# schematic.net
KiCad netlist of a schematic drawn in EAGLE
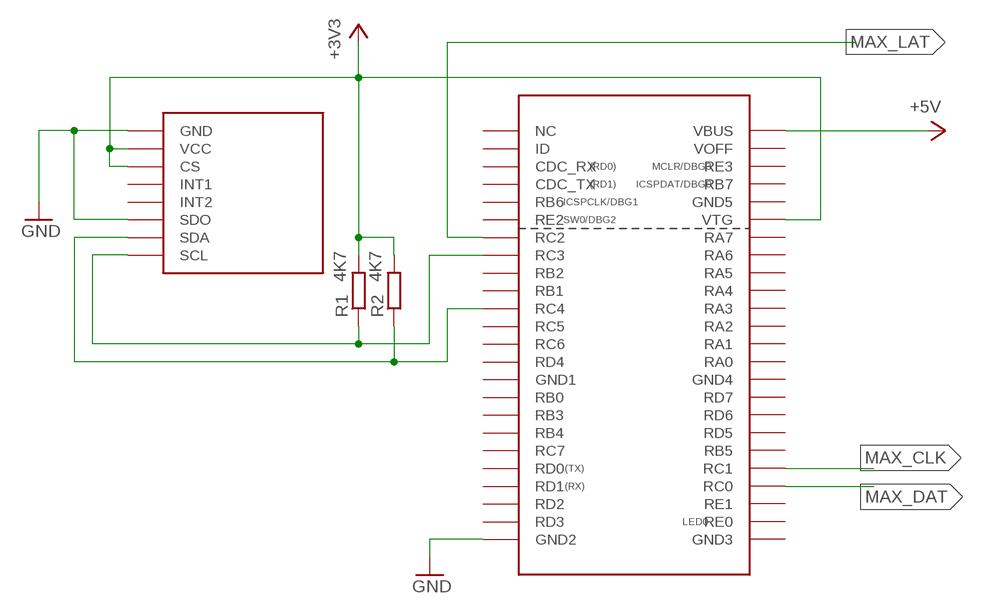
[diagram p0: schematic, sheet 1]

(export (version "E")
  (design (tool "Eeschema 10.0.6"))
  (components
    (comp (ref "R1")
      (value "4K7")
      (footprint "eagle-import:0204_5")
      (libsource (lib "eagle-import") (part "R-EU_0204/5"))
    )
    (comp (ref "R2")
      (value "4K7")
      (footprint "eagle-import:0204_5")
      (libsource (lib "eagle-import") (part "R-EU_0204/5"))
    )
    (comp (ref "U$1")
      (value "PIC16F15376_CURIOSITY_NANO")
      (footprint "eagle-import:48PIN_CURIOSITY_NANO")
      (libsource (lib "eagle-import") (part "PIC16F15376_CURIOSITY_NANO"))
    )
    (comp (ref "U$2")
      (value "ADXL345_SPARKFUN")
      (footprint "eagle-import:ADXL345_SPARKFUN")
      (libsource (lib "eagle-import") (part "ADXL345_SPARKFUN"))
    )
  )
  (nets
    (net (code "1") (name "+3V3") (class "Default")
      (node (ref "R1") (pin "2") (pinfunction "2_2") (pintype "passive"))
      (node (ref "R2") (pin "2") (pinfunction "2_2") (pintype "passive"))
      (node (ref "U$1") (pin "P$43") (pinfunction "VTG_P$43") (pintype "power_in"))
      (node (ref "U$2") (pin "P$2") (pinfunction "VCC_P$2") (pintype "power_in"))
      (node (ref "U$2") (pin "P$3") (pinfunction "CS_P$3") (pintype "bidirectional"))
    )
    (net (code "2") (name "+5V") (class "Default")
      (node (ref "U$1") (pin "P$48") (pinfunction "VBUS_P$48") (pintype "power_in"))
    )
    (net (code "3") (name "/GND1") (class "Default")
      (node (ref "U$1") (pin "P$15") (pinfunction "GND1_P$15") (pintype "power_in"))
    )
    (net (code "4") (name "/GND5") (class "Default")
      (node (ref "U$1") (pin "P$44") (pinfunction "GND5_P$44") (pintype "power_in"))
    )
    (net (code "5") (name "/VOFF") (class "Default")
      (node (ref "U$1") (pin "P$47") (pinfunction "VOFF_P$47") (pintype "power_in"))
    )
    (net (code "6") (name "GND") (class "Default")
      (node (ref "U$1") (pin "P$24") (pinfunction "GND2_P$24") (pintype "bidirectional"))
      (node (ref "U$2") (pin "P$1") (pinfunction "GND_P$1") (pintype "power_in"))
      (node (ref "U$2") (pin "P$6") (pinfunction "SDO_P$6") (pintype "bidirectional"))
    )
    (net (code "7") (name "MAX_CLK") (class "Default")
      (node (ref "U$1") (pin "P$29") (pinfunction "RC1_P$29") (pintype "bidirectional"))
    )
    (net (code "8") (name "MAX_DAT") (class "Default")
      (node (ref "U$1") (pin "P$28") (pinfunction "RC0_P$28") (pintype "bidirectional"))
    )
    (net (code "9") (name "MAX_LAT") (class "Default")
      (node (ref "U$1") (pin "P$7") (pinfunction "RC2_P$7") (pintype "bidirectional"))
    )
    (net (code "10") (name "Net-(U$1-RC3)") (class "Default")
      (node (ref "R1") (pin "1") (pinfunction "1_1") (pintype "passive"))
      (node (ref "U$1") (pin "P$8") (pinfunction "RC3_P$8") (pintype "bidirectional"))
      (node (ref "U$2") (pin "P$8") (pinfunction "SCL_P$8") (pintype "bidirectional"))
    )
    (net (code "11") (name "Net-(U$1-RC4)") (class "Default")
      (node (ref "R2") (pin "1") (pinfunction "1_1") (pintype "passive"))
      (node (ref "U$1") (pin "P$11") (pinfunction "RC4_P$11") (pintype "bidirectional"))
      (node (ref "U$2") (pin "P$7") (pinfunction "SDA_P$7") (pintype "bidirectional"))
    )
    (net (code "12") (name "unconnected-(U$1-CDC_RX-PadP$3)") (class "Default")
      (node (ref "U$1") (pin "P$3") (pinfunction "CDC_RX_P$3") (pintype "bidirectional"))
    )
    (net (code "13") (name "unconnected-(U$1-CDC_TX-PadP$4)") (class "Default")
      (node (ref "U$1") (pin "P$4") (pinfunction "CDC_TX_P$4") (pintype "bidirectional"))
    )
    (net (code "14") (name "unconnected-(U$1-GND3-PadP$25)") (class "Default")
      (node (ref "U$1") (pin "P$25") (pinfunction "GND3_P$25") (pintype "bidirectional"))
    )
    (net (code "15") (name "unconnected-(U$1-GND4-PadP$34)") (class "Default")
      (node (ref "U$1") (pin "P$34") (pinfunction "GND4_P$34") (pintype "bidirectional"))
    )
    (net (code "16") (name "unconnected-(U$1-ID-PadP$2)") (class "Default")
      (node (ref "U$1") (pin "P$2") (pinfunction "ID_P$2") (pintype "bidirectional"))
    )
    (net (code "17") (name "unconnected-(U$1-NC-PadP$1)") (class "Default")
      (node (ref "U$1") (pin "P$1") (pinfunction "NC_P$1") (pintype "no_connect"))
    )
    (net (code "18") (name "unconnected-(U$1-RA0-PadP$35)") (class "Default")
      (node (ref "U$1") (pin "P$35") (pinfunction "RA0_P$35") (pintype "bidirectional"))
    )
    (net (code "19") (name "unconnected-(U$1-RA1-PadP$36)") (class "Default")
      (node (ref "U$1") (pin "P$36") (pinfunction "RA1_P$36") (pintype "bidirectional"))
    )
    (net (code "20") (name "unconnected-(U$1-RA2-PadP$37)") (class "Default")
      (node (ref "U$1") (pin "P$37") (pinfunction "RA2_P$37") (pintype "bidirectional"))
    )
    (net (code "21") (name "unconnected-(U$1-RA3-PadP$38)") (class "Default")
      (node (ref "U$1") (pin "P$38") (pinfunction "RA3_P$38") (pintype "bidirectional"))
    )
    (net (code "22") (name "unconnected-(U$1-RA4-PadP$39)") (class "Default")
      (node (ref "U$1") (pin "P$39") (pinfunction "RA4_P$39") (pintype "bidirectional"))
    )
    (net (code "23") (name "unconnected-(U$1-RA5-PadP$40)") (class "Default")
      (node (ref "U$1") (pin "P$40") (pinfunction "RA5_P$40") (pintype "bidirectional"))
    )
    (net (code "24") (name "unconnected-(U$1-RA6-PadP$41)") (class "Default")
      (node (ref "U$1") (pin "P$41") (pinfunction "RA6_P$41") (pintype "bidirectional"))
    )
    (net (code "25") (name "unconnected-(U$1-RA7-PadP$42)") (class "Default")
      (node (ref "U$1") (pin "P$42") (pinfunction "RA7_P$42") (pintype "bidirectional"))
    )
    (net (code "26") (name "unconnected-(U$1-RB0-PadP$16)") (class "Default")
      (node (ref "U$1") (pin "P$16") (pinfunction "RB0_P$16") (pintype "bidirectional"))
    )
    (net (code "27") (name "unconnected-(U$1-RB1-PadP$10)") (class "Default")
      (node (ref "U$1") (pin "P$10") (pinfunction "RB1_P$10") (pintype "bidirectional"))
    )
    (net (code "28") (name "unconnected-(U$1-RB2-PadP$9)") (class "Default")
      (node (ref "U$1") (pin "P$9") (pinfunction "RB2_P$9") (pintype "bidirectional"))
    )
    (net (code "29") (name "unconnected-(U$1-RB3-PadP$17)") (class "Default")
      (node (ref "U$1") (pin "P$17") (pinfunction "RB3_P$17") (pintype "bidirectional"))
    )
    (net (code "30") (name "unconnected-(U$1-RB4-PadP$18)") (class "Default")
      (node (ref "U$1") (pin "P$18") (pinfunction "RB4_P$18") (pintype "bidirectional"))
    )
    (net (code "31") (name "unconnected-(U$1-RB5-PadP$30)") (class "Default")
      (node (ref "U$1") (pin "P$30") (pinfunction "RB5_P$30") (pintype "bidirectional"))
    )
    (net (code "32") (name "unconnected-(U$1-RB6-PadP$5)") (class "Default")
      (node (ref "U$1") (pin "P$5") (pinfunction "RB6_P$5") (pintype "bidirectional"))
    )
    (net (code "33") (name "unconnected-(U$1-RB7-PadP$45)") (class "Default")
      (node (ref "U$1") (pin "P$45") (pinfunction "RB7_P$45") (pintype "bidirectional"))
    )
    (net (code "34") (name "unconnected-(U$1-RC5-PadP$12)") (class "Default")
      (node (ref "U$1") (pin "P$12") (pinfunction "RC5_P$12") (pintype "bidirectional"))
    )
    (net (code "35") (name "unconnected-(U$1-RC6-PadP$13)") (class "Default")
      (node (ref "U$1") (pin "P$13") (pinfunction "RC6_P$13") (pintype "bidirectional"))
    )
    (net (code "36") (name "unconnected-(U$1-RC7-PadP$19)") (class "Default")
      (node (ref "U$1") (pin "P$19") (pinfunction "RC7_P$19") (pintype "bidirectional"))
    )
    (net (code "37") (name "unconnected-(U$1-RD0-PadP$20)") (class "Default")
      (node (ref "U$1") (pin "P$20") (pinfunction "RD0_P$20") (pintype "bidirectional"))
    )
    (net (code "38") (name "unconnected-(U$1-RD1-PadP$21)") (class "Default")
      (node (ref "U$1") (pin "P$21") (pinfunction "RD1_P$21") (pintype "bidirectional"))
    )
    (net (code "39") (name "unconnected-(U$1-RD2-PadP$22)") (class "Default")
      (node (ref "U$1") (pin "P$22") (pinfunction "RD2_P$22") (pintype "bidirectional"))
    )
    (net (code "40") (name "unconnected-(U$1-RD3-PadP$23)") (class "Default")
      (node (ref "U$1") (pin "P$23") (pinfunction "RD3_P$23") (pintype "bidirectional"))
    )
    (net (code "41") (name "unconnected-(U$1-RD4-PadP$14)") (class "Default")
      (node (ref "U$1") (pin "P$14") (pinfunction "RD4_P$14") (pintype "bidirectional"))
    )
    (net (code "42") (name "unconnected-(U$1-RD5-PadP$31)") (class "Default")
      (node (ref "U$1") (pin "P$31") (pinfunction "RD5_P$31") (pintype "bidirectional"))
    )
    (net (code "43") (name "unconnected-(U$1-RD6-PadP$32)") (class "Default")
      (node (ref "U$1") (pin "P$32") (pinfunction "RD6_P$32") (pintype "bidirectional"))
    )
    (net (code "44") (name "unconnected-(U$1-RD7-PadP$33)") (class "Default")
      (node (ref "U$1") (pin "P$33") (pinfunction "RD7_P$33") (pintype "bidirectional"))
    )
    (net (code "45") (name "unconnected-(U$1-RE0-PadP$26)") (class "Default")
      (node (ref "U$1") (pin "P$26") (pinfunction "RE0_P$26") (pintype "bidirectional"))
    )
    (net (code "46") (name "unconnected-(U$1-RE1-PadP$27)") (class "Default")
      (node (ref "U$1") (pin "P$27") (pinfunction "RE1_P$27") (pintype "bidirectional"))
    )
    (net (code "47") (name "unconnected-(U$1-RE2-PadP$6)") (class "Default")
      (node (ref "U$1") (pin "P$6") (pinfunction "RE2_P$6") (pintype "bidirectional"))
    )
    (net (code "48") (name "unconnected-(U$1-RE3-PadP$46)") (class "Default")
      (node (ref "U$1") (pin "P$46") (pinfunction "RE3_P$46") (pintype "bidirectional"))
    )
    (net (code "49") (name "unconnected-(U$2-INT1-PadP$4)") (class "Default")
      (node (ref "U$2") (pin "P$4") (pinfunction "INT1_P$4") (pintype "bidirectional"))
    )
    (net (code "50") (name "unconnected-(U$2-INT2-PadP$5)") (class "Default")
      (node (ref "U$2") (pin "P$5") (pinfunction "INT2_P$5") (pintype "bidirectional"))
    )
  )
)
